# Tray3.net
KiCad netlist of a schematic drawn in Altium Designer
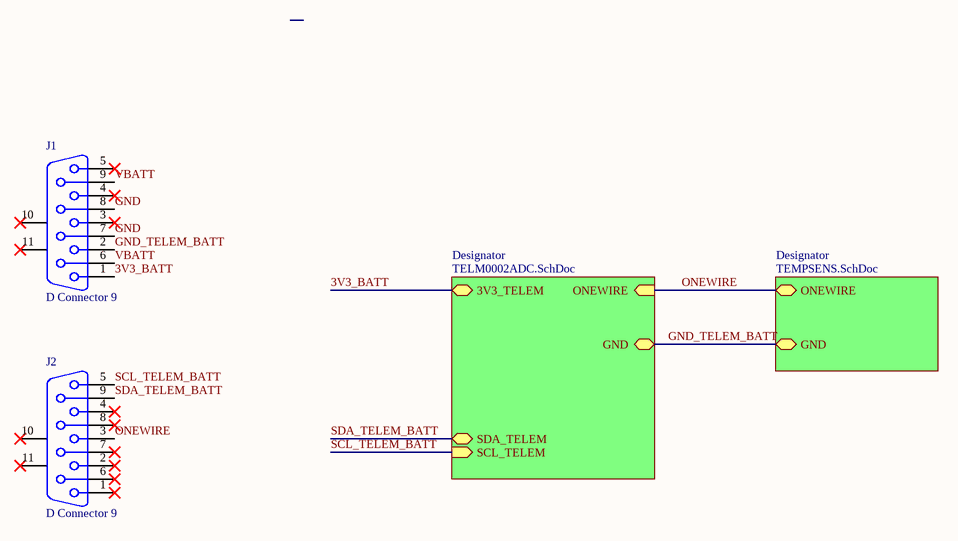
[diagram p0: Tray3.SchDoc]

(export (version "E")
  (design (tool "Eeschema 10.0.6"))
  (components
    (comp (ref "J1")
      (value "D Connector 9")
      (footprint "DSUB1.385-2H9")
      (description "Receptacle Assembly, 9 Position, Right Angle")
      (fields (field (name "PUBLISHER") "Altium Limited"))
      (libsource (lib "Miscellaneous Connectors") (part "D Connector 9"))
    )
    (comp (ref "J2")
      (value "D Connector 9")
      (footprint "DSUB1.385-2H9")
      (description "Receptacle Assembly, 9 Position, Right Angle")
      (fields (field (name "PUBLISHER") "Altium Limited"))
      (libsource (lib "Miscellaneous Connectors") (part "D Connector 9"))
    )
  )
  (nets
    (net (code "1") (name "/3V3_BATT") (class "Default")
      (node (ref "J1") (pin "1") (pinfunction "1_1") (pintype "passive"))
    )
    (net (code "2") (name "/GND") (class "Default")
      (node (ref "J1") (pin "7") (pinfunction "7_7") (pintype "passive"))
      (node (ref "J1") (pin "8") (pinfunction "8_8") (pintype "passive"))
    )
    (net (code "3") (name "/GND_TELEM_BATT") (class "Default")
      (node (ref "J1") (pin "2") (pinfunction "2_2") (pintype "passive"))
    )
    (net (code "4") (name "/ONEWIRE") (class "Default")
      (node (ref "J2") (pin "3") (pinfunction "3_3") (pintype "passive"))
    )
    (net (code "5") (name "/SCL_TELEM_BATT") (class "Default")
      (node (ref "J2") (pin "5") (pinfunction "5_5") (pintype "passive"))
    )
    (net (code "6") (name "/SDA_TELEM_BATT") (class "Default")
      (node (ref "J2") (pin "9") (pinfunction "9_9") (pintype "passive"))
    )
    (net (code "7") (name "/VBATT") (class "Default")
      (node (ref "J1") (pin "6") (pinfunction "6_6") (pintype "passive"))
      (node (ref "J1") (pin "9") (pinfunction "9_9") (pintype "passive"))
    )
    (net (code "8") (name "unconnected-(J1-MH1-Pad10)") (class "Default")
      (node (ref "J1") (pin "10") (pinfunction "MH1_10") (pintype "passive+no_connect"))
    )
    (net (code "9") (name "unconnected-(J1-MH2-Pad11)") (class "Default")
      (node (ref "J1") (pin "11") (pinfunction "MH2_11") (pintype "passive+no_connect"))
    )
    (net (code "10") (name "unconnected-(J1-Pad3)") (class "Default")
      (node (ref "J1") (pin "3") (pinfunction "3_3") (pintype "passive+no_connect"))
    )
    (net (code "11") (name "unconnected-(J1-Pad4)") (class "Default")
      (node (ref "J1") (pin "4") (pinfunction "4_4") (pintype "passive+no_connect"))
    )
    (net (code "12") (name "unconnected-(J1-Pad5)") (class "Default")
      (node (ref "J1") (pin "5") (pinfunction "5_5") (pintype "passive+no_connect"))
    )
    (net (code "13") (name "unconnected-(J2-MH1-Pad10)") (class "Default")
      (node (ref "J2") (pin "10") (pinfunction "MH1_10") (pintype "passive+no_connect"))
    )
    (net (code "14") (name "unconnected-(J2-MH2-Pad11)") (class "Default")
      (node (ref "J2") (pin "11") (pinfunction "MH2_11") (pintype "passive+no_connect"))
    )
    (net (code "15") (name "unconnected-(J2-Pad1)") (class "Default")
      (node (ref "J2") (pin "1") (pinfunction "1_1") (pintype "passive+no_connect"))
    )
    (net (code "16") (name "unconnected-(J2-Pad2)") (class "Default")
      (node (ref "J2") (pin "2") (pinfunction "2_2") (pintype "passive+no_connect"))
    )
    (net (code "17") (name "unconnected-(J2-Pad4)") (class "Default")
      (node (ref "J2") (pin "4") (pinfunction "4_4") (pintype "passive+no_connect"))
    )
    (net (code "18") (name "unconnected-(J2-Pad6)") (class "Default")
      (node (ref "J2") (pin "6") (pinfunction "6_6") (pintype "passive+no_connect"))
    )
    (net (code "19") (name "unconnected-(J2-Pad7)") (class "Default")
      (node (ref "J2") (pin "7") (pinfunction "7_7") (pintype "passive+no_connect"))
    )
    (net (code "20") (name "unconnected-(J2-Pad8)") (class "Default")
      (node (ref "J2") (pin "8") (pinfunction "8_8") (pintype "passive+no_connect"))
    )
  )
)
